# board.net
KiCad netlist of a schematic drawn in EAGLE
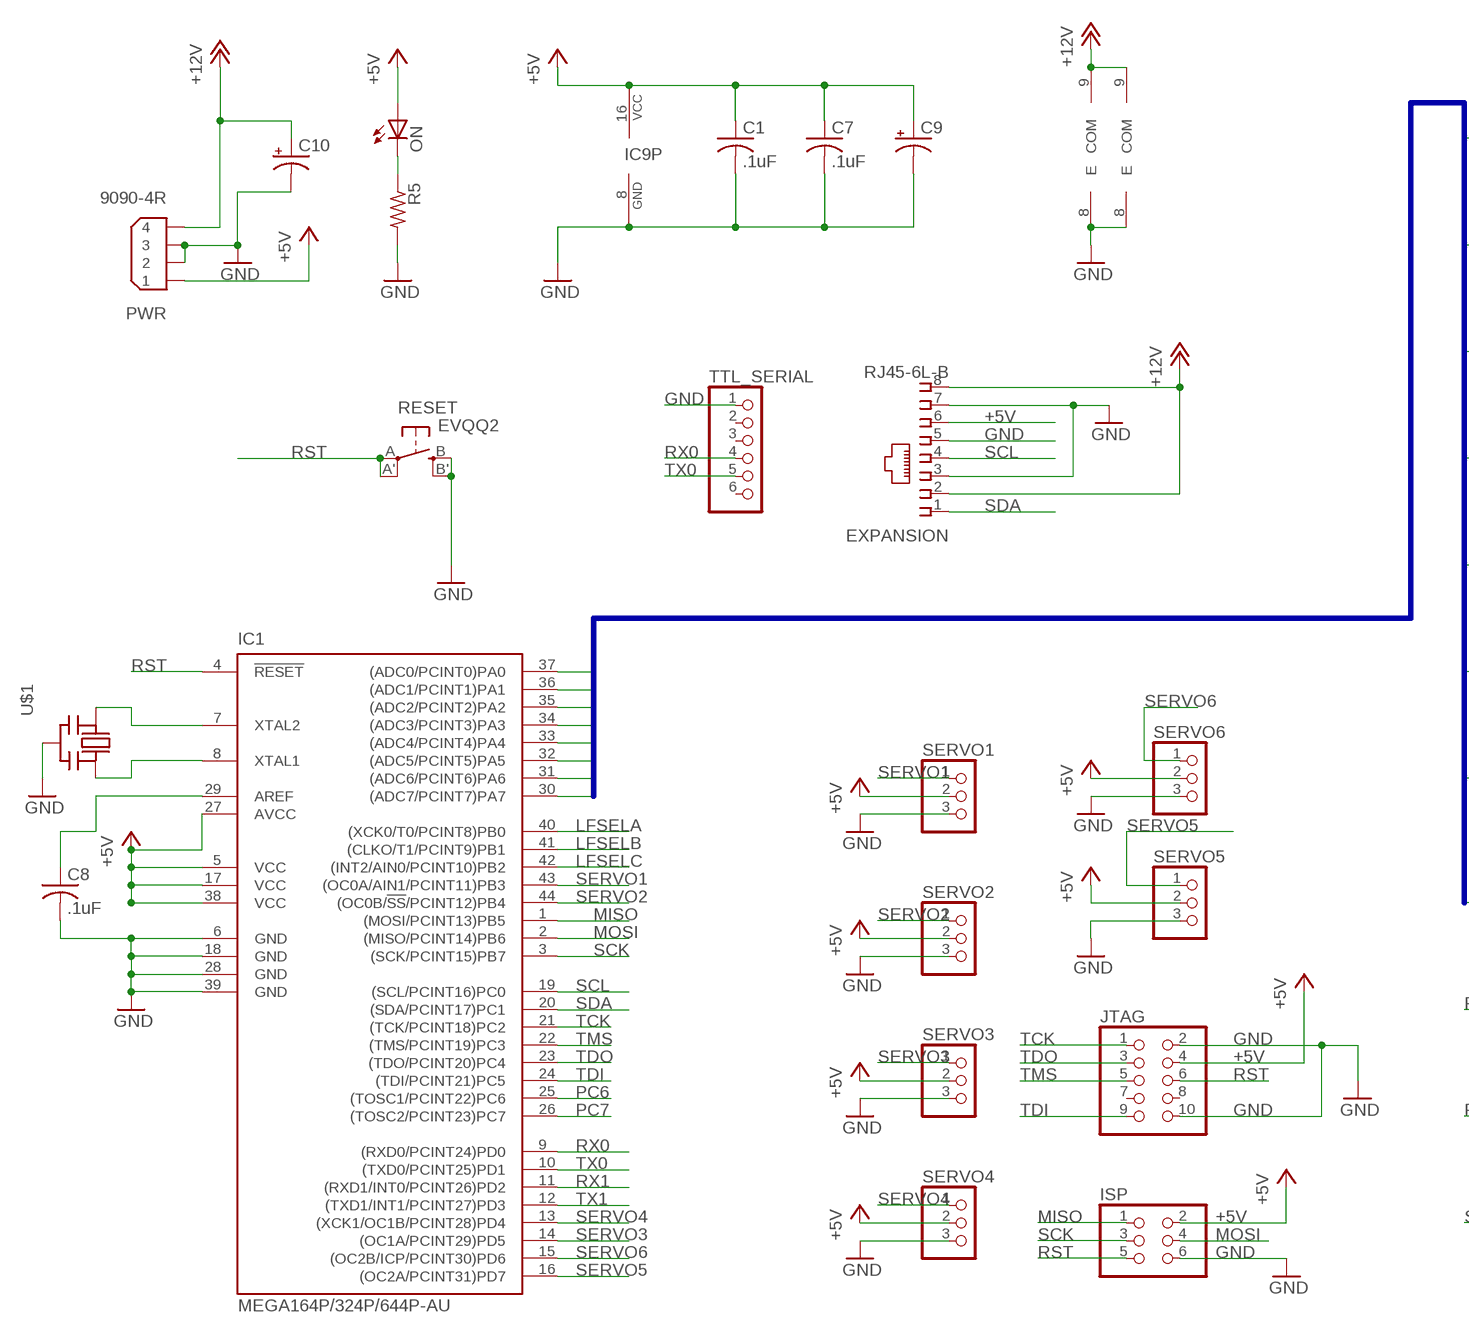
[diagram p0: schematic, sheet 1, part 1 of 2]
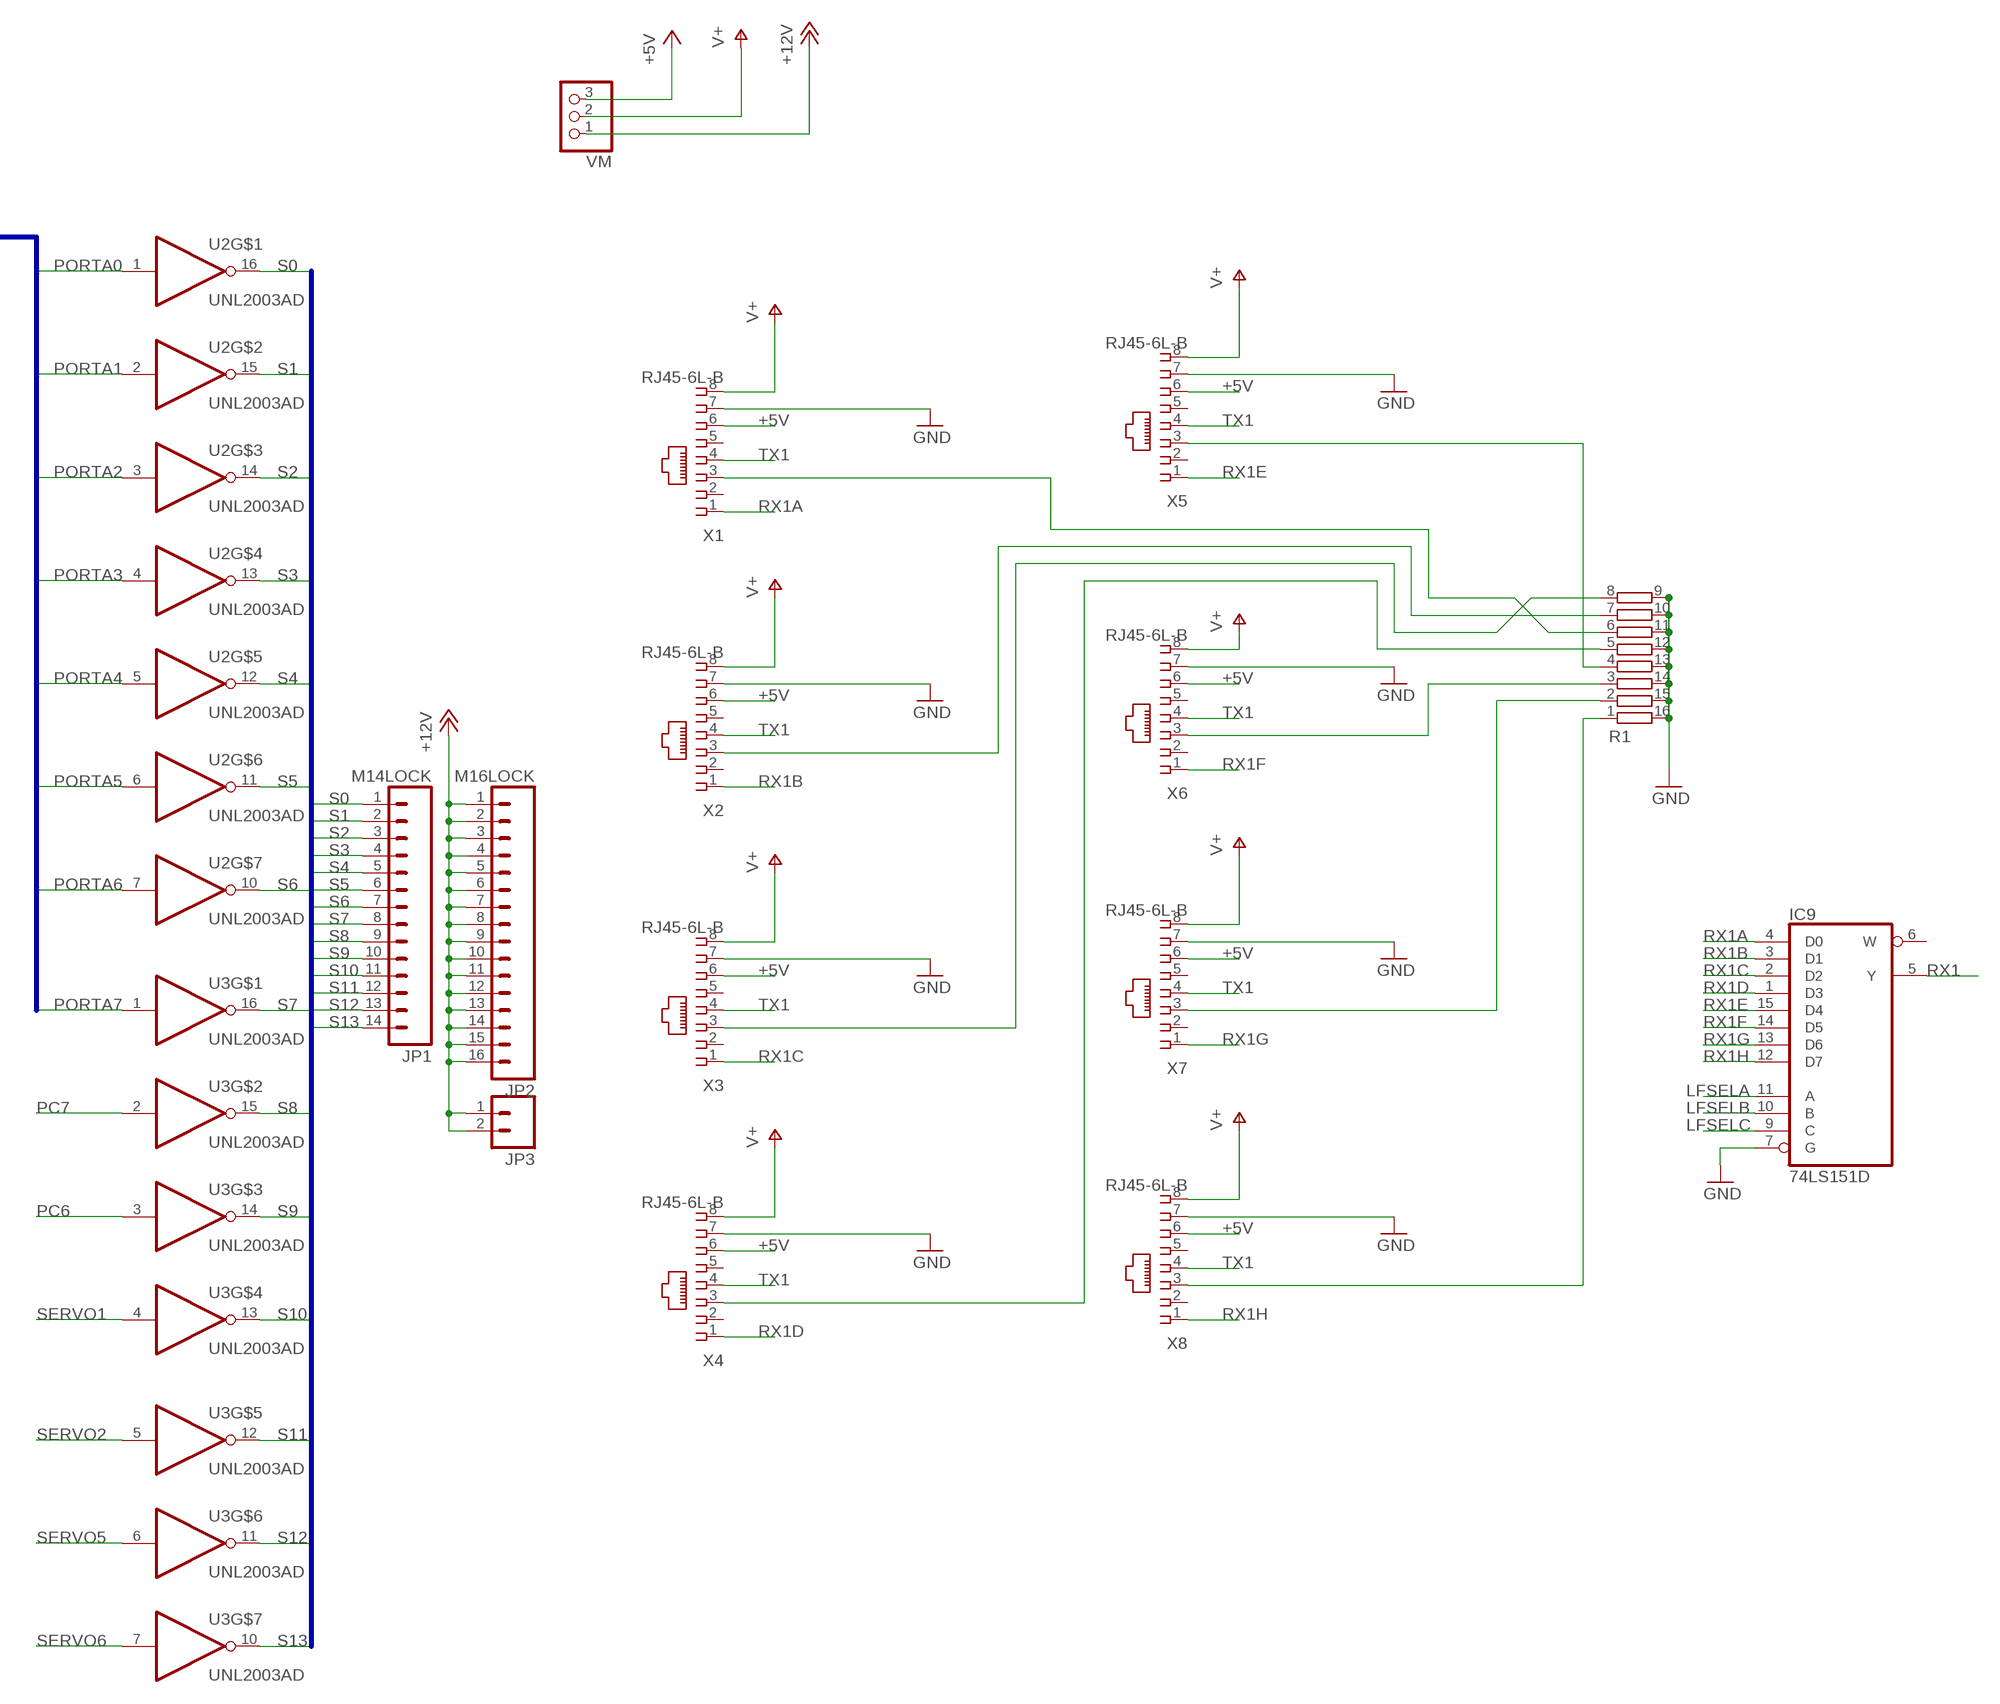
[diagram p1: schematic, sheet 1, part 2 of 2]

(export (version "E")
  (design (tool "Eeschema 10.0.6"))
  (components
    (comp (ref "C1")
      (value ".1uF")
      (footprint "eagle-import:C0805")
      (libsource (lib "eagle-import") (part "C-USC0805"))
    )
    (comp (ref "C7")
      (value ".1uF")
      (footprint "eagle-import:C0805")
      (libsource (lib "eagle-import") (part "C-USC0805"))
    )
    (comp (ref "C8")
      (value ".1uF")
      (footprint "eagle-import:C0805")
      (libsource (lib "eagle-import") (part "C-USC0805"))
    )
    (comp (ref "C9")
      (value "CPOL-USE2.5-7")
      (footprint "eagle-import:E2,5-7")
      (libsource (lib "eagle-import") (part "CPOL-USE2.5-7"))
    )
    (comp (ref "C10")
      (value "CPOL-USE2.5-7")
      (footprint "eagle-import:E2,5-7")
      (libsource (lib "eagle-import") (part "CPOL-USE2.5-7"))
    )
    (comp (ref "EXPANSION")
      (value "RJ45-6L-B")
      (footprint "eagle-import:RJ45-NO-SHIELD")
      (libsource (lib "eagle-import") (part "RJ45-6L-B"))
    )
    (comp (ref "IC1")
      (value "MEGA164P/324P/644P-AU")
      (footprint "eagle-import:TQFP44")
      (libsource (lib "eagle-import") (part "MEGA164P/324P/644P-AU"))
    )
    (comp (ref "IC9")
      (value "74LS151D")
      (footprint "eagle-import:SO16")
      (libsource (lib "eagle-import") (part "74151DLS"))
    )
    (comp (ref "ISP")
      (value "PINHD-2X3")
      (footprint "eagle-import:2X03")
      (libsource (lib "eagle-import") (part "PINHD-2X3"))
    )
    (comp (ref "JP1")
      (value "M14LOCK")
      (footprint "eagle-import:1X14_LOCK")
      (libsource (lib "eagle-import") (part "M14LOCK"))
    )
    (comp (ref "JP2")
      (value "M16LOCK")
      (footprint "eagle-import:1X16_LOCK")
      (libsource (lib "eagle-import") (part "M16LOCK"))
    )
    (comp (ref "JP3")
      (value "M02PTH")
      (footprint "eagle-import:1X02")
      (libsource (lib "eagle-import") (part "M02PTH"))
    )
    (comp (ref "JTAG")
      (value "PINHD-2X5")
      (footprint "eagle-import:2X05")
      (libsource (lib "eagle-import") (part "PINHD-2X5"))
    )
    (comp (ref "ON")
      (value "LEDCHIPLED_0805")
      (footprint "eagle-import:CHIPLED_0805")
      (libsource (lib "eagle-import") (part "LEDCHIPLED_0805"))
    )
    (comp (ref "PWR")
      (value "9090-4R")
      (footprint "eagle-import:9090-4R")
      (libsource (lib "eagle-import") (part "9090-4R"))
    )
    (comp (ref "R1")
      (value "2NBS16-8")
      (footprint "eagle-import:SO16")
      (libsource (lib "eagle-import") (part "2NBS16-8"))
    )
    (comp (ref "R5")
      (value "R-US_R0805")
      (footprint "eagle-import:R0805")
      (libsource (lib "eagle-import") (part "R-US_R0805"))
    )
    (comp (ref "RESET")
      (value "EVQQ2")
      (footprint "eagle-import:EVQ-Q2")
      (libsource (lib "eagle-import") (part "EVQQ2"))
    )
    (comp (ref "SERVO1")
      (value "PINHD-1X3")
      (footprint "eagle-import:1X03")
      (libsource (lib "eagle-import") (part "PINHD-1X3"))
    )
    (comp (ref "SERVO2")
      (value "PINHD-1X3")
      (footprint "eagle-import:1X03")
      (libsource (lib "eagle-import") (part "PINHD-1X3"))
    )
    (comp (ref "SERVO3")
      (value "PINHD-1X3")
      (footprint "eagle-import:1X03")
      (libsource (lib "eagle-import") (part "PINHD-1X3"))
    )
    (comp (ref "SERVO4")
      (value "PINHD-1X3")
      (footprint "eagle-import:1X03")
      (libsource (lib "eagle-import") (part "PINHD-1X3"))
    )
    (comp (ref "SERVO5")
      (value "PINHD-1X3")
      (footprint "eagle-import:1X03")
      (libsource (lib "eagle-import") (part "PINHD-1X3"))
    )
    (comp (ref "SERVO6")
      (value "PINHD-1X3")
      (footprint "eagle-import:1X03")
      (libsource (lib "eagle-import") (part "PINHD-1X3"))
    )
    (comp (ref "TTL_SERIAL")
      (value "PINHD-1X6")
      (footprint "eagle-import:1X06")
      (libsource (lib "eagle-import") (part "PINHD-1X6"))
    )
    (comp (ref "U$1")
      (value "CERMOSCILL-CSTCRG")
      (footprint "eagle-import:CSTCR-G")
      (libsource (lib "eagle-import") (part "CERMOSCILL-CSTCRG"))
    )
    (comp (ref "U2")
      (value "UNL2003AD")
      (footprint "eagle-import:SO16")
      (libsource (lib "eagle-import") (part "UNL2003AD"))
    )
    (comp (ref "U3")
      (value "UNL2003AD")
      (footprint "eagle-import:SO16")
      (libsource (lib "eagle-import") (part "UNL2003AD"))
    )
    (comp (ref "VM")
      (value "PINHD-1X3")
      (footprint "eagle-import:1X03")
      (libsource (lib "eagle-import") (part "PINHD-1X3"))
    )
    (comp (ref "X1")
      (value "RJ45-6L-B")
      (footprint "eagle-import:RJ45-NO-SHIELD")
      (libsource (lib "eagle-import") (part "RJ45-6L-B"))
    )
    (comp (ref "X2")
      (value "RJ45-6L-B")
      (footprint "eagle-import:RJ45-NO-SHIELD")
      (libsource (lib "eagle-import") (part "RJ45-6L-B"))
    )
    (comp (ref "X3")
      (value "RJ45-6L-B")
      (footprint "eagle-import:RJ45-NO-SHIELD")
      (libsource (lib "eagle-import") (part "RJ45-6L-B"))
    )
    (comp (ref "X4")
      (value "RJ45-6L-B")
      (footprint "eagle-import:RJ45-NO-SHIELD")
      (libsource (lib "eagle-import") (part "RJ45-6L-B"))
    )
    (comp (ref "X5")
      (value "RJ45-6L-B")
      (footprint "eagle-import:RJ45-NO-SHIELD")
      (libsource (lib "eagle-import") (part "RJ45-6L-B"))
    )
    (comp (ref "X6")
      (value "RJ45-6L-B")
      (footprint "eagle-import:RJ45-NO-SHIELD")
      (libsource (lib "eagle-import") (part "RJ45-6L-B"))
    )
    (comp (ref "X7")
      (value "RJ45-6L-B")
      (footprint "eagle-import:RJ45-NO-SHIELD")
      (libsource (lib "eagle-import") (part "RJ45-6L-B"))
    )
    (comp (ref "X8")
      (value "RJ45-6L-B")
      (footprint "eagle-import:RJ45-NO-SHIELD")
      (libsource (lib "eagle-import") (part "RJ45-6L-B"))
    )
  )
  (nets
    (net (code "1") (name "+5V") (class "Default")
      (node (ref "C1") (pin "1") (pinfunction "1_1") (pintype "passive"))
      (node (ref "C7") (pin "1") (pinfunction "1_1") (pintype "passive"))
      (node (ref "C9") (pin "+") (pinfunction "+_+") (pintype "passive"))
      (node (ref "EXPANSION") (pin "6") (pinfunction "6_6") (pintype "passive"))
      (node (ref "IC1") (pin "17") (pinfunction "VCC_17") (pintype "power_in"))
      (node (ref "IC1") (pin "27") (pinfunction "AVCC_27") (pintype "power_in"))
      (node (ref "IC1") (pin "38") (pinfunction "VCC_38") (pintype "power_in"))
      (node (ref "IC1") (pin "5") (pinfunction "VCC_5") (pintype "power_in"))
      (node (ref "IC9") (pin "16") (pinfunction "VCC_16") (pintype "power_in"))
      (node (ref "ISP") (pin "2") (pinfunction "2_2") (pintype "passive"))
      (node (ref "JTAG") (pin "4") (pinfunction "4_4") (pintype "passive"))
      (node (ref "ON") (pin "A") (pinfunction "A_A") (pintype "passive"))
      (node (ref "PWR") (pin "1") (pinfunction "1_1") (pintype "passive"))
      (node (ref "SERVO1") (pin "2") (pinfunction "2_2") (pintype "passive"))
      (node (ref "SERVO2") (pin "2") (pinfunction "2_2") (pintype "passive"))
      (node (ref "SERVO3") (pin "2") (pinfunction "2_2") (pintype "passive"))
      (node (ref "SERVO4") (pin "2") (pinfunction "2_2") (pintype "passive"))
      (node (ref "SERVO5") (pin "2") (pinfunction "2_2") (pintype "passive"))
      (node (ref "SERVO6") (pin "2") (pinfunction "2_2") (pintype "passive"))
      (node (ref "VM") (pin "3") (pinfunction "3_3") (pintype "passive"))
      (node (ref "X1") (pin "6") (pinfunction "6_6") (pintype "passive"))
      (node (ref "X2") (pin "6") (pinfunction "6_6") (pintype "passive"))
      (node (ref "X3") (pin "6") (pinfunction "6_6") (pintype "passive"))
      (node (ref "X4") (pin "6") (pinfunction "6_6") (pintype "passive"))
      (node (ref "X5") (pin "6") (pinfunction "6_6") (pintype "passive"))
      (node (ref "X6") (pin "6") (pinfunction "6_6") (pintype "passive"))
      (node (ref "X7") (pin "6") (pinfunction "6_6") (pintype "passive"))
      (node (ref "X8") (pin "6") (pinfunction "6_6") (pintype "passive"))
    )
    (net (code "2") (name "+12V") (class "Default")
      (node (ref "C10") (pin "+") (pinfunction "+_+") (pintype "passive"))
      (node (ref "EXPANSION") (pin "2") (pinfunction "2_2") (pintype "passive"))
      (node (ref "EXPANSION") (pin "8") (pinfunction "8_8") (pintype "passive"))
      (node (ref "JP2") (pin "1") (pinfunction "1_1") (pintype "passive"))
      (node (ref "JP2") (pin "10") (pinfunction "10_10") (pintype "passive"))
      (node (ref "JP2") (pin "11") (pinfunction "11_11") (pintype "passive"))
      (node (ref "JP2") (pin "12") (pinfunction "12_12") (pintype "passive"))
      (node (ref "JP2") (pin "13") (pinfunction "13_13") (pintype "passive"))
      (node (ref "JP2") (pin "14") (pinfunction "14_14") (pintype "passive"))
      (node (ref "JP2") (pin "15") (pinfunction "15_15") (pintype "passive"))
      (node (ref "JP2") (pin "16") (pinfunction "16_16") (pintype "passive"))
      (node (ref "JP2") (pin "2") (pinfunction "2_2") (pintype "passive"))
      (node (ref "JP2") (pin "3") (pinfunction "3_3") (pintype "passive"))
      (node (ref "JP2") (pin "4") (pinfunction "4_4") (pintype "passive"))
      (node (ref "JP2") (pin "5") (pinfunction "5_5") (pintype "passive"))
      (node (ref "JP2") (pin "6") (pinfunction "6_6") (pintype "passive"))
      (node (ref "JP2") (pin "7") (pinfunction "7_7") (pintype "passive"))
      (node (ref "JP2") (pin "8") (pinfunction "8_8") (pintype "passive"))
      (node (ref "JP2") (pin "9") (pinfunction "9_9") (pintype "passive"))
      (node (ref "JP3") (pin "1") (pinfunction "1_1") (pintype "passive"))
      (node (ref "JP3") (pin "2") (pinfunction "2_2") (pintype "passive"))
      (node (ref "PWR") (pin "4") (pinfunction "4_4") (pintype "passive"))
      (node (ref "U2") (pin "9") (pinfunction "COM_9") (pintype "power_in"))
      (node (ref "U3") (pin "9") (pinfunction "COM_9") (pintype "power_in"))
      (node (ref "VM") (pin "1") (pinfunction "1_1") (pintype "passive"))
    )
    (net (code "3") (name "/LFSELA") (class "Default")
      (node (ref "IC1") (pin "40") (pinfunction "(XCK0/T0/PCINT8)PB0_40") (pintype "bidirectional"))
      (node (ref "IC9") (pin "11") (pinfunction "A_11") (pintype "input"))
    )
    (net (code "4") (name "/LFSELB") (class "Default")
      (node (ref "IC1") (pin "41") (pinfunction "(CLKO/T1/PCINT9)PB1_41") (pintype "bidirectional"))
      (node (ref "IC9") (pin "10") (pinfunction "B_10") (pintype "input"))
    )
    (net (code "5") (name "/LFSELC") (class "Default")
      (node (ref "IC1") (pin "42") (pinfunction "(INT2/AIN0/PCINT10)PB2_42") (pintype "bidirectional"))
      (node (ref "IC9") (pin "9") (pinfunction "C_9") (pintype "input"))
    )
    (net (code "6") (name "/MISO") (class "Default")
      (node (ref "IC1") (pin "1") (pinfunction "(MOSI/PCINT13)PB5_1") (pintype "bidirectional"))
      (node (ref "ISP") (pin "1") (pinfunction "1_1") (pintype "passive"))
    )
    (net (code "7") (name "/MOSI") (class "Default")
      (node (ref "IC1") (pin "2") (pinfunction "(MISO/PCINT14)PB6_2") (pintype "bidirectional"))
      (node (ref "ISP") (pin "4") (pinfunction "4_4") (pintype "passive"))
    )
    (net (code "8") (name "/PC6") (class "Default")
      (node (ref "IC1") (pin "25") (pinfunction "(TOSC1/PCINT22)PC6_25") (pintype "bidirectional"))
      (node (ref "U3") (pin "3") (pinfunction "I_3") (pintype "input"))
    )
    (net (code "9") (name "/PC7") (class "Default")
      (node (ref "IC1") (pin "26") (pinfunction "(TOSC2/PCINT23)PC7_26") (pintype "bidirectional"))
      (node (ref "U3") (pin "2") (pinfunction "I_2") (pintype "input"))
    )
    (net (code "10") (name "/PORTA0") (class "Default")
      (node (ref "IC1") (pin "37") (pinfunction "(ADC0/PCINT0)PA0_37") (pintype "bidirectional"))
      (node (ref "U2") (pin "1") (pinfunction "I_1") (pintype "input"))
    )
    (net (code "11") (name "/PORTA1") (class "Default")
      (node (ref "IC1") (pin "36") (pinfunction "(ADC1/PCINT1)PA1_36") (pintype "bidirectional"))
      (node (ref "U2") (pin "2") (pinfunction "I_2") (pintype "input"))
    )
    (net (code "12") (name "/PORTA2") (class "Default")
      (node (ref "IC1") (pin "35") (pinfunction "(ADC2/PCINT2)PA2_35") (pintype "bidirectional"))
      (node (ref "U2") (pin "3") (pinfunction "I_3") (pintype "input"))
    )
    (net (code "13") (name "/PORTA3") (class "Default")
      (node (ref "IC1") (pin "34") (pinfunction "(ADC3/PCINT3)PA3_34") (pintype "bidirectional"))
      (node (ref "U2") (pin "4") (pinfunction "I_4") (pintype "input"))
    )
    (net (code "14") (name "/PORTA4") (class "Default")
      (node (ref "IC1") (pin "33") (pinfunction "(ADC4/PCINT4)PA4_33") (pintype "bidirectional"))
      (node (ref "U2") (pin "5") (pinfunction "I_5") (pintype "input"))
    )
    (net (code "15") (name "/PORTA5") (class "Default")
      (node (ref "IC1") (pin "32") (pinfunction "(ADC5/PCINT5)PA5_32") (pintype "bidirectional"))
      (node (ref "U2") (pin "6") (pinfunction "I_6") (pintype "input"))
    )
    (net (code "16") (name "/PORTA6") (class "Default")
      (node (ref "IC1") (pin "31") (pinfunction "(ADC6/PCINT6)PA6_31") (pintype "bidirectional"))
      (node (ref "U2") (pin "7") (pinfunction "I_7") (pintype "input"))
    )
    (net (code "17") (name "/PORTA7") (class "Default")
      (node (ref "IC1") (pin "30") (pinfunction "(ADC7/PCINT7)PA7_30") (pintype "bidirectional"))
      (node (ref "U3") (pin "1") (pinfunction "I_1") (pintype "input"))
    )
    (net (code "18") (name "/RST") (class "Default")
      (node (ref "IC1") (pin "4") (pinfunction "~{RESET}_4") (pintype "input"))
      (node (ref "ISP") (pin "5") (pinfunction "5_5") (pintype "passive"))
      (node (ref "JTAG") (pin "6") (pinfunction "6_6") (pintype "passive"))
      (node (ref "RESET") (pin "A") (pinfunction "P_A") (pintype "passive"))
      (node (ref "RESET") (pin "A'") (pinfunction "P1_A'") (pintype "passive"))
    )
    (net (code "19") (name "/RX0") (class "Default")
      (node (ref "IC1") (pin "9") (pinfunction "(RXD0/PCINT24)PD0_9") (pintype "bidirectional"))
      (node (ref "TTL_SERIAL") (pin "4") (pinfunction "4_4") (pintype "passive"))
    )
    (net (code "20") (name "/RX1") (class "Default")
      (node (ref "IC1") (pin "11") (pinfunction "(RXD1/INT0/PCINT26)PD2_11") (pintype "bidirectional"))
      (node (ref "IC9") (pin "5") (pinfunction "Y_5") (pintype "output"))
    )
    (net (code "21") (name "/RX1A") (class "Default")
      (node (ref "IC9") (pin "4") (pinfunction "D0_4") (pintype "input"))
      (node (ref "X1") (pin "1") (pinfunction "1_1") (pintype "passive"))
    )
    (net (code "22") (name "/RX1B") (class "Default")
      (node (ref "IC9") (pin "3") (pinfunction "D1_3") (pintype "input"))
      (node (ref "X2") (pin "1") (pinfunction "1_1") (pintype "passive"))
    )
    (net (code "23") (name "/RX1C") (class "Default")
      (node (ref "IC9") (pin "2") (pinfunction "D2_2") (pintype "input"))
      (node (ref "X3") (pin "1") (pinfunction "1_1") (pintype "passive"))
    )
    (net (code "24") (name "/RX1D") (class "Default")
      (node (ref "IC9") (pin "1") (pinfunction "D3_1") (pintype "input"))
      (node (ref "X4") (pin "1") (pinfunction "1_1") (pintype "passive"))
    )
    (net (code "25") (name "/RX1E") (class "Default")
      (node (ref "IC9") (pin "15") (pinfunction "D4_15") (pintype "input"))
      (node (ref "X5") (pin "1") (pinfunction "1_1") (pintype "passive"))
    )
    (net (code "26") (name "/RX1F") (class "Default")
      (node (ref "IC9") (pin "14") (pinfunction "D5_14") (pintype "input"))
      (node (ref "X6") (pin "1") (pinfunction "1_1") (pintype "passive"))
    )
    (net (code "27") (name "/RX1G") (class "Default")
      (node (ref "IC9") (pin "13") (pinfunction "D6_13") (pintype "input"))
      (node (ref "X7") (pin "1") (pinfunction "1_1") (pintype "passive"))
    )
    (net (code "28") (name "/RX1H") (class "Default")
      (node (ref "IC9") (pin "12") (pinfunction "D7_12") (pintype "input"))
      (node (ref "X8") (pin "1") (pinfunction "1_1") (pintype "passive"))
    )
    (net (code "29") (name "/S0") (class "Default")
      (node (ref "JP1") (pin "1") (pinfunction "1_1") (pintype "passive"))
      (node (ref "U2") (pin "16") (pinfunction "O_16") (pintype "output"))
    )
    (net (code "30") (name "/S1") (class "Default")
      (node (ref "JP1") (pin "2") (pinfunction "2_2") (pintype "passive"))
      (node (ref "U2") (pin "15") (pinfunction "O_15") (pintype "output"))
    )
    (net (code "31") (name "/S2") (class "Default")
      (node (ref "JP1") (pin "3") (pinfunction "3_3") (pintype "passive"))
      (node (ref "U2") (pin "14") (pinfunction "O_14") (pintype "output"))
    )
    (net (code "32") (name "/S3") (class "Default")
      (node (ref "JP1") (pin "4") (pinfunction "4_4") (pintype "passive"))
      (node (ref "U2") (pin "13") (pinfunction "O_13") (pintype "output"))
    )
    (net (code "33") (name "/S4") (class "Default")
      (node (ref "JP1") (pin "5") (pinfunction "5_5") (pintype "passive"))
      (node (ref "U2") (pin "12") (pinfunction "O_12") (pintype "output"))
    )
    (net (code "34") (name "/S5") (class "Default")
      (node (ref "JP1") (pin "6") (pinfunction "6_6") (pintype "passive"))
      (node (ref "U2") (pin "11") (pinfunction "O_11") (pintype "output"))
    )
    (net (code "35") (name "/S6") (class "Default")
      (node (ref "JP1") (pin "7") (pinfunction "7_7") (pintype "passive"))
      (node (ref "U2") (pin "10") (pinfunction "O_10") (pintype "output"))
    )
    (net (code "36") (name "/S7") (class "Default")
      (node (ref "JP1") (pin "8") (pinfunction "8_8") (pintype "passive"))
      (node (ref "U3") (pin "16") (pinfunction "O_16") (pintype "output"))
    )
    (net (code "37") (name "/S8") (class "Default")
      (node (ref "JP1") (pin "9") (pinfunction "9_9") (pintype "passive"))
      (node (ref "U3") (pin "15") (pinfunction "O_15") (pintype "output"))
    )
    (net (code "38") (name "/S9") (class "Default")
      (node (ref "JP1") (pin "10") (pinfunction "10_10") (pintype "passive"))
      (node (ref "U3") (pin "14") (pinfunction "O_14") (pintype "output"))
    )
    (net (code "39") (name "/S10") (class "Default")
      (node (ref "JP1") (pin "11") (pinfunction "11_11") (pintype "passive"))
      (node (ref "U3") (pin "13") (pinfunction "O_13") (pintype "output"))
    )
    (net (code "40") (name "/S11") (class "Default")
      (node (ref "JP1") (pin "12") (pinfunction "12_12") (pintype "passive"))
      (node (ref "U3") (pin "12") (pinfunction "O_12") (pintype "output"))
    )
    (net (code "41") (name "/S12") (class "Default")
      (node (ref "JP1") (pin "13") (pinfunction "13_13") (pintype "passive"))
      (node (ref "U3") (pin "11") (pinfunction "O_11") (pintype "output"))
    )
    (net (code "42") (name "/S13") (class "Default")
      (node (ref "JP1") (pin "14") (pinfunction "14_14") (pintype "passive"))
      (node (ref "U3") (pin "10") (pinfunction "O_10") (pintype "output"))
    )
    (net (code "43") (name "/SCK") (class "Default")
      (node (ref "IC1") (pin "3") (pinfunction "(SCK/PCINT15)PB7_3") (pintype "bidirectional"))
      (node (ref "ISP") (pin "3") (pinfunction "3_3") (pintype "passive"))
    )
    (net (code "44") (name "/SCL") (class "Default")
      (node (ref "EXPANSION") (pin "4") (pinfunction "4_4") (pintype "passive"))
      (node (ref "IC1") (pin "19") (pinfunction "(SCL/PCINT16)PC0_19") (pintype "bidirectional"))
    )
    (net (code "45") (name "/SDA") (class "Default")
      (node (ref "EXPANSION") (pin "1") (pinfunction "1_1") (pintype "passive"))
      (node (ref "IC1") (pin "20") (pinfunction "(SDA/PCINT17)PC1_20") (pintype "bidirectional"))
    )
    (net (code "46") (name "/SERVO1") (class "Default")
      (node (ref "IC1") (pin "43") (pinfunction "(OC0A/AIN1/PCINT11)PB3_43") (pintype "bidirectional"))
      (node (ref "SERVO1") (pin "1") (pinfunction "1_1") (pintype "passive"))
      (node (ref "U3") (pin "4") (pinfunction "I_4") (pintype "input"))
    )
    (net (code "47") (name "/SERVO2") (class "Default")
      (node (ref "IC1") (pin "44") (pinfunction "(OC0B/~{SS}/PCINT12)PB4_44") (pintype "bidirectional"))
      (node (ref "SERVO2") (pin "1") (pinfunction "1_1") (pintype "passive"))
      (node (ref "U3") (pin "5") (pinfunction "I_5") (pintype "input"))
    )
    (net (code "48") (name "/SERVO3") (class "Default")
      (node (ref "IC1") (pin "14") (pinfunction "(OC1A/PCINT29)PD5_14") (pintype "bidirectional"))
      (node (ref "SERVO3") (pin "1") (pinfunction "1_1") (pintype "passive"))
    )
    (net (code "49") (name "/SERVO4") (class "Default")
      (node (ref "IC1") (pin "13") (pinfunction "(XCK1/OC1B/PCINT28)PD4_13") (pintype "bidirectional"))
      (node (ref "SERVO4") (pin "1") (pinfunction "1_1") (pintype "passive"))
    )
    (net (code "50") (name "/SERVO5") (class "Default")
      (node (ref "IC1") (pin "16") (pinfunction "(OC2A/PCINT31)PD7_16") (pintype "bidirectional"))
      (node (ref "SERVO5") (pin "1") (pinfunction "1_1") (pintype "passive"))
      (node (ref "U3") (pin "6") (pinfunction "I_6") (pintype "input"))
    )
    (net (code "51") (name "/SERVO6") (class "Default")
      (node (ref "IC1") (pin "15") (pinfunction "(OC2B/ICP/PCINT30)PD6_15") (pintype "bidirectional"))
      (node (ref "SERVO6") (pin "1") (pinfunction "1_1") (pintype "passive"))
      (node (ref "U3") (pin "7") (pinfunction "I_7") (pintype "input"))
    )
    (net (code "52") (name "/TCK") (class "Default")
      (node (ref "IC1") (pin "21") (pinfunction "(TCK/PCINT18)PC2_21") (pintype "bidirectional"))
      (node (ref "JTAG") (pin "1") (pinfunction "1_1") (pintype "passive"))
    )
    (net (code "53") (name "/TDI") (class "Default")
      (node (ref "IC1") (pin "24") (pinfunction "(TDI/PCINT21)PC5_24") (pintype "bidirectional"))
      (node (ref "JTAG") (pin "9") (pinfunction "9_9") (pintype "passive"))
    )
    (net (code "54") (name "/TDO") (class "Default")
      (node (ref "IC1") (pin "23") (pinfunction "(TDO/PCINT20)PC4_23") (pintype "bidirectional"))
      (node (ref "JTAG") (pin "3") (pinfunction "3_3") (pintype "passive"))
    )
    (net (code "55") (name "/TMS") (class "Default")
      (node (ref "IC1") (pin "22") (pinfunction "(TMS/PCINT19)PC3_22") (pintype "bidirectional"))
      (node (ref "JTAG") (pin "5") (pinfunction "5_5") (pintype "passive"))
    )
    (net (code "56") (name "/TX0") (class "Default")
      (node (ref "IC1") (pin "10") (pinfunction "(TXD0/PCINT25)PD1_10") (pintype "bidirectional"))
      (node (ref "TTL_SERIAL") (pin "5") (pinfunction "5_5") (pintype "passive"))
    )
    (net (code "57") (name "/TX1") (class "Default")
      (node (ref "IC1") (pin "12") (pinfunction "(TXD1/INT1/PCINT27)PD3_12") (pintype "bidirectional"))
      (node (ref "X1") (pin "4") (pinfunction "4_4") (pintype "passive"))
      (node (ref "X2") (pin "4") (pinfunction "4_4") (pintype "passive"))
      (node (ref "X3") (pin "4") (pinfunction "4_4") (pintype "passive"))
      (node (ref "X4") (pin "4") (pinfunction "4_4") (pintype "passive"))
      (node (ref "X5") (pin "4") (pinfunction "4_4") (pintype "passive"))
      (node (ref "X6") (pin "4") (pinfunction "4_4") (pintype "passive"))
      (node (ref "X7") (pin "4") (pinfunction "4_4") (pintype "passive"))
      (node (ref "X8") (pin "4") (pinfunction "4_4") (pintype "passive"))
    )
    (net (code "58") (name "GND") (class "Default")
      (node (ref "C1") (pin "2") (pinfunction "2_2") (pintype "passive"))
      (node (ref "C10") (pin "-") (pinfunction "-_-") (pintype "passive"))
      (node (ref "C7") (pin "2") (pinfunction "2_2") (pintype "passive"))
      (node (ref "C8") (pin "2") (pinfunction "2_2") (pintype "passive"))
      (node (ref "C9") (pin "-") (pinfunction "-_-") (pintype "passive"))
      (node (ref "EXPANSION") (pin "3") (pinfunction "3_3") (pintype "passive"))
      (node (ref "EXPANSION") (pin "5") (pinfunction "5_5") (pintype "passive"))
      (node (ref "EXPANSION") (pin "7") (pinfunction "7_7") (pintype "passive"))
      (node (ref "IC1") (pin "18") (pinfunction "GND_18") (pintype "power_in"))
      (node (ref "IC1") (pin "28") (pinfunction "GND_28") (pintype "power_in"))
      (node (ref "IC1") (pin "39") (pinfunction "GND_39") (pintype "power_in"))
      (node (ref "IC1") (pin "6") (pinfunction "GND_6") (pintype "power_in"))
      (node (ref "IC9") (pin "7") (pinfunction "G_7") (pintype "input"))
      (node (ref "IC9") (pin "8") (pinfunction "GND_8") (pintype "power_in"))
      (node (ref "ISP") (pin "6") (pinfunction "6_6") (pintype "passive"))
      (node (ref "JTAG") (pin "10") (pinfunction "10_10") (pintype "passive"))
      (node (ref "JTAG") (pin "2") (pinfunction "2_2") (pintype "passive"))
      (node (ref "PWR") (pin "2") (pinfunction "2_2") (pintype "passive"))
      (node (ref "PWR") (pin "3") (pinfunction "3_3") (pintype "passive"))
      (node (ref "R1") (pin "10") (pinfunction "10_10") (pintype "passive"))
      (node (ref "R1") (pin "11") (pinfunction "11_11") (pintype "passive"))
      (node (ref "R1") (pin "12") (pinfunction "12_12") (pintype "passive"))
      (node (ref "R1") (pin "13") (pinfunction "13_13") (pintype "passive"))
      (node (ref "R1") (pin "14") (pinfunction "14_14") (pintype "passive"))
      (node (ref "R1") (pin "15") (pinfunction "15_15") (pintype "passive"))
      (node (ref "R1") (pin "16") (pinfunction "16_16") (pintype "passive"))
      (node (ref "R1") (pin "9") (pinfunction "9_9") (pintype "passive"))
      (node (ref "R5") (pin "2") (pinfunction "2_2") (pintype "passive"))
      (node (ref "RESET") (pin "B") (pinfunction "S_B") (pintype "passive"))
      (node (ref "RESET") (pin "B'") (pinfunction "S1_B'") (pintype "passive"))
      (node (ref "SERVO1") (pin "3") (pinfunction "3_3") (pintype "passive"))
      (node (ref "SERVO2") (pin "3") (pinfunction "3_3") (pintype "passive"))
      (node (ref "SERVO3") (pin "3") (pinfunction "3_3") (pintype "passive"))
      (node (ref "SERVO4") (pin "3") (pinfunction "3_3") (pintype "passive"))
      (node (ref "SERVO5") (pin "3") (pinfunction "3_3") (pintype "passive"))
      (node (ref "SERVO6") (pin "3") (pinfunction "3_3") (pintype "passive"))
      (node (ref "TTL_SERIAL") (pin "1") (pinfunction "1_1") (pintype "passive"))
      (node (ref "U$1") (pin "2") (pinfunction "GND_2") (pintype "bidirectional"))
      (node (ref "U2") (pin "8") (pinfunction "E_8") (pintype "power_in"))
      (node (ref "U3") (pin "8") (pinfunction "E_8") (pintype "power_in"))
      (node (ref "X1") (pin "7") (pinfunction "7_7") (pintype "passive"))
      (node (ref "X2") (pin "7") (pinfunction "7_7") (pintype "passive"))
      (node (ref "X3") (pin "7") (pinfunction "7_7") (pintype "passive"))
      (node (ref "X4") (pin "7") (pinfunction "7_7") (pintype "passive"))
      (node (ref "X5") (pin "7") (pinfunction "7_7") (pintype "passive"))
      (node (ref "X6") (pin "7") (pinfunction "7_7") (pintype "passive"))
      (node (ref "X7") (pin "7") (pinfunction "7_7") (pintype "passive"))
      (node (ref "X8") (pin "7") (pinfunction "7_7") (pintype "passive"))
    )
    (net (code "59") (name "Net-(IC1-AREF)") (class "Default")
      (node (ref "C8") (pin "1") (pinfunction "1_1") (pintype "passive"))
      (node (ref "IC1") (pin "29") (pinfunction "AREF_29") (pintype "power_in"))
    )
    (net (code "60") (name "Net-(IC1-XTAL1)") (class "Default")
      (node (ref "IC1") (pin "8") (pinfunction "XTAL1_8") (pintype "input"))
      (node (ref "U$1") (pin "3") (pinfunction "OUT_3") (pintype "bidirectional"))
    )
    (net (code "61") (name "Net-(IC1-XTAL2)") (class "Default")
      (node (ref "IC1") (pin "7") (pinfunction "XTAL2_7") (pintype "output"))
      (node (ref "U$1") (pin "1") (pinfunction "IN_1") (pintype "bidirectional"))
    )
    (net (code "62") (name "Net-(ON-PadC)") (class "Default")
      (node (ref "ON") (pin "C") (pinfunction "C_C") (pintype "passive"))
      (node (ref "R5") (pin "1") (pinfunction "1_1") (pintype "passive"))
    )
    (net (code "63") (name "Net-(R1-Pad1)") (class "Default")
      (node (ref "R1") (pin "1") (pinfunction "1_1") (pintype "passive"))
      (node (ref "X8") (pin "3") (pinfunction "3_3") (pintype "passive"))
    )
    (net (code "64") (name "Net-(R1-Pad2)") (class "Default")
      (node (ref "R1") (pin "2") (pinfunction "2_2") (pintype "passive"))
      (node (ref "X7") (pin "3") (pinfunction "3_3") (pintype "passive"))
    )
    (net (code "65") (name "Net-(R1-Pad3)") (class "Default")
      (node (ref "R1") (pin "3") (pinfunction "3_3") (pintype "passive"))
      (node (ref "X6") (pin "3") (pinfunction "3_3") (pintype "passive"))
    )
    (net (code "66") (name "Net-(R1-Pad4)") (class "Default")
      (node (ref "R1") (pin "4") (pinfunction "4_4") (pintype "passive"))
      (node (ref "X5") (pin "3") (pinfunction "3_3") (pintype "passive"))
    )
    (net (code "67") (name "Net-(R1-Pad5)") (class "Default")
      (node (ref "R1") (pin "5") (pinfunction "5_5") (pintype "passive"))
      (node (ref "X4") (pin "3") (pinfunction "3_3") (pintype "passive"))
    )
    (net (code "68") (name "Net-(R1-Pad6)") (class "Default")
      (node (ref "R1") (pin "6") (pinfunction "6_6") (pintype "passive"))
      (node (ref "X1") (pin "3") (pinfunction "3_3") (pintype "passive"))
    )
    (net (code "69") (name "Net-(R1-Pad7)") (class "Default")
      (node (ref "R1") (pin "7") (pinfunction "7_7") (pintype "passive"))
      (node (ref "X2") (pin "3") (pinfunction "3_3") (pintype "passive"))
    )
    (net (code "70") (name "Net-(R1-Pad8)") (class "Default")
      (node (ref "R1") (pin "8") (pinfunction "8_8") (pintype "passive"))
      (node (ref "X3") (pin "3") (pinfunction "3_3") (pintype "passive"))
    )
    (net (code "71") (name "V+") (class "Default")
      (node (ref "VM") (pin "2") (pinfunction "2_2") (pintype "passive"))
      (node (ref "X1") (pin "8") (pinfunction "8_8") (pintype "passive"))
      (node (ref "X2") (pin "8") (pinfunction "8_8") (pintype "passive"))
      (node (ref "X3") (pin "8") (pinfunction "8_8") (pintype "passive"))
      (node (ref "X4") (pin "8") (pinfunction "8_8") (pintype "passive"))
      (node (ref "X5") (pin "8") (pinfunction "8_8") (pintype "passive"))
      (node (ref "X6") (pin "8") (pinfunction "8_8") (pintype "passive"))
      (node (ref "X7") (pin "8") (pinfunction "8_8") (pintype "passive"))
      (node (ref "X8") (pin "8") (pinfunction "8_8") (pintype "passive"))
    )
    (net (code "72") (name "unconnected-(IC9A-W-Pad6)") (class "Default")
      (node (ref "IC9") (pin "6") (pinfunction "W_6") (pintype "output"))
    )
    (net (code "73") (name "unconnected-(JTAG-Pad7)") (class "Default")
      (node (ref "JTAG") (pin "7") (pinfunction "7_7") (pintype "passive"))
    )
    (net (code "74") (name "unconnected-(JTAG-Pad8)") (class "Default")
      (node (ref "JTAG") (pin "8") (pinfunction "8_8") (pintype "passive"))
    )
    (net (code "75") (name "unconnected-(TTL_SERIAL-Pad2)") (class "Default")
      (node (ref "TTL_SERIAL") (pin "2") (pinfunction "2_2") (pintype "passive"))
    )
    (net (code "76") (name "unconnected-(TTL_SERIAL-Pad3)") (class "Default")
      (node (ref "TTL_SERIAL") (pin "3") (pinfunction "3_3") (pintype "passive"))
    )
    (net (code "77") (name "unconnected-(TTL_SERIAL-Pad6)") (class "Default")
      (node (ref "TTL_SERIAL") (pin "6") (pinfunction "6_6") (pintype "passive"))
    )
    (net (code "78") (name "unconnected-(X1-Pad2)") (class "Default")
      (node (ref "X1") (pin "2") (pinfunction "2_2") (pintype "passive"))
    )
    (net (code "79") (name "unconnected-(X1-Pad5)") (class "Default")
      (node (ref "X1") (pin "5") (pinfunction "5_5") (pintype "passive"))
    )
    (net (code "80") (name "unconnected-(X2-Pad2)") (class "Default")
      (node (ref "X2") (pin "2") (pinfunction "2_2") (pintype "passive"))
    )
    (net (code "81") (name "unconnected-(X2-Pad5)") (class "Default")
      (node (ref "X2") (pin "5") (pinfunction "5_5") (pintype "passive"))
    )
    (net (code "82") (name "unconnected-(X3-Pad2)") (class "Default")
      (node (ref "X3") (pin "2") (pinfunction "2_2") (pintype "passive"))
    )
    (net (code "83") (name "unconnected-(X3-Pad5)") (class "Default")
      (node (ref "X3") (pin "5") (pinfunction "5_5") (pintype "passive"))
    )
    (net (code "84") (name "unconnected-(X4-Pad2)") (class "Default")
      (node (ref "X4") (pin "2") (pinfunction "2_2") (pintype "passive"))
    )
    (net (code "85") (name "unconnected-(X4-Pad5)") (class "Default")
      (node (ref "X4") (pin "5") (pinfunction "5_5") (pintype "passive"))
    )
    (net (code "86") (name "unconnected-(X5-Pad2)") (class "Default")
      (node (ref "X5") (pin "2") (pinfunction "2_2") (pintype "passive"))
    )
    (net (code "87") (name "unconnected-(X5-Pad5)") (class "Default")
      (node (ref "X5") (pin "5") (pinfunction "5_5") (pintype "passive"))
    )
    (net (code "88") (name "unconnected-(X6-Pad2)") (class "Default")
      (node (ref "X6") (pin "2") (pinfunction "2_2") (pintype "passive"))
    )
    (net (code "89") (name "unconnected-(X6-Pad5)") (class "Default")
      (node (ref "X6") (pin "5") (pinfunction "5_5") (pintype "passive"))
    )
    (net (code "90") (name "unconnected-(X7-Pad2)") (class "Default")
      (node (ref "X7") (pin "2") (pinfunction "2_2") (pintype "passive"))
    )
    (net (code "91") (name "unconnected-(X7-Pad5)") (class "Default")
      (node (ref "X7") (pin "5") (pinfunction "5_5") (pintype "passive"))
    )
    (net (code "92") (name "unconnected-(X8-Pad2)") (class "Default")
      (node (ref "X8") (pin "2") (pinfunction "2_2") (pintype "passive"))
    )
    (net (code "93") (name "unconnected-(X8-Pad5)") (class "Default")
      (node (ref "X8") (pin "5") (pinfunction "5_5") (pintype "passive"))
    )
  )
)
